# MicroSD.net
KiCad netlist of a schematic drawn in Altium Designer
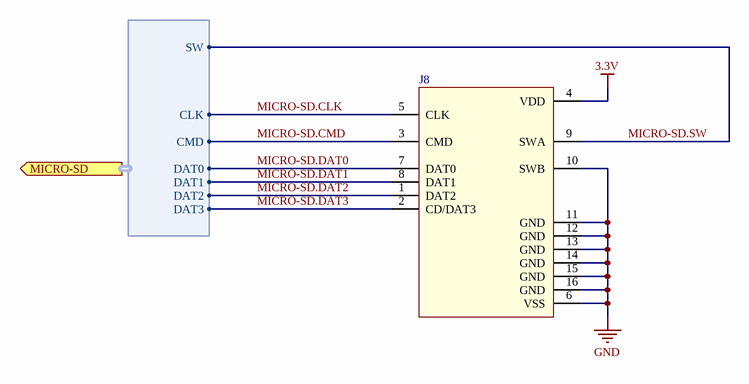
[diagram p0: MicroSD.SchDoc]

(export (version "E")
  (design (tool "Eeschema 10.0.6"))
  (components
    (comp (ref "J8")
      (value "~")
      (footprint "TE-2201778-1")
      (description "Conn Memory Card RCP 8 POS 1.1mm Solder RA SMD 0.5A/Contact T/R")
      (libsource (lib "TeConnectivity") (part "2201778-1"))
    )
  )
  (nets
    (net (code "2") (name "/MICRO-SD.CLK") (class "Default")
      (node (ref "J8") (pin "5") (pinfunction "CLK_5") (pintype "power_in"))
    )
    (net (code "3") (name "/MICRO-SD.CMD") (class "Default")
      (node (ref "J8") (pin "3") (pinfunction "CMD_3") (pintype "power_in"))
    )
    (net (code "4") (name "/MICRO-SD.DAT0") (class "Default")
      (node (ref "J8") (pin "7") (pinfunction "DAT0_7") (pintype "power_in"))
    )
    (net (code "5") (name "/MICRO-SD.DAT1") (class "Default")
      (node (ref "J8") (pin "8") (pinfunction "DAT1_8") (pintype "power_in"))
    )
    (net (code "6") (name "/MICRO-SD.DAT2") (class "Default")
      (node (ref "J8") (pin "1") (pinfunction "DAT2_1") (pintype "power_in"))
    )
    (net (code "7") (name "/MICRO-SD.DAT3") (class "Default")
      (node (ref "J8") (pin "2") (pinfunction "CD/DAT3_2") (pintype "power_in"))
    )
    (net (code "8") (name "/MICRO-SD.SW") (class "Default")
      (node (ref "J8") (pin "9") (pinfunction "SWA_9") (pintype "passive"))
    )
    (net (code "10") (name "3.3V") (class "Default")
      (node (ref "J8") (pin "4") (pinfunction "VDD_4") (pintype "power_in"))
    )
    (net (code "11") (name "GND") (class "Default")
      (node (ref "J8") (pin "10") (pinfunction "SWB_10") (pintype "passive"))
      (node (ref "J8") (pin "11") (pinfunction "GND_11") (pintype "power_in"))
      (node (ref "J8") (pin "12") (pinfunction "GND_12") (pintype "power_in"))
      (node (ref "J8") (pin "13") (pinfunction "GND_13") (pintype "power_in"))
      (node (ref "J8") (pin "14") (pinfunction "GND_14") (pintype "power_in"))
      (node (ref "J8") (pin "15") (pinfunction "GND_15") (pintype "power_in"))
      (node (ref "J8") (pin "16") (pinfunction "GND_16") (pintype "power_in"))
      (node (ref "J8") (pin "6") (pinfunction "VSS_6") (pintype "power_in"))
    )
  )
)
